# SLIM-MO-64.net
KiCad netlist of a schematic drawn in EAGLE
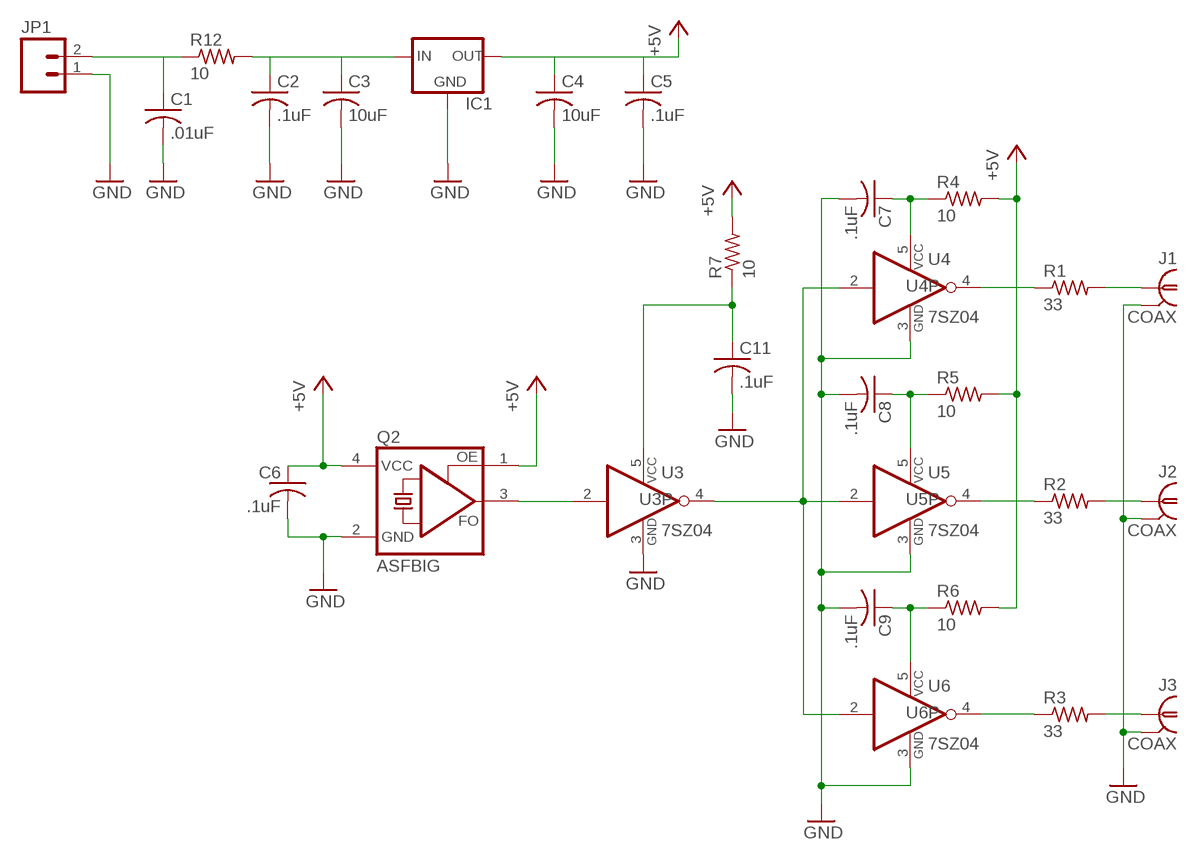
[diagram p0: schematic, sheet 1]

(export (version "E")
  (design (tool "Eeschema 10.0.6"))
  (components
    (comp (ref "C1")
      (value ".01uF")
      (footprint "eagle-import:C0805")
      (libsource (lib "eagle-import") (part "C-USC0805"))
    )
    (comp (ref "C2")
      (value ".1uF")
      (footprint "eagle-import:C0805")
      (libsource (lib "eagle-import") (part "C-USC0805"))
    )
    (comp (ref "C3")
      (value "10uF")
      (footprint "eagle-import:C1206")
      (libsource (lib "eagle-import") (part "C-USC1206"))
    )
    (comp (ref "C4")
      (value "10uF")
      (footprint "eagle-import:C1206")
      (libsource (lib "eagle-import") (part "C-USC1206"))
    )
    (comp (ref "C5")
      (value ".1uF")
      (footprint "eagle-import:C0805")
      (libsource (lib "eagle-import") (part "C-USC0805"))
    )
    (comp (ref "C6")
      (value ".1uF")
      (footprint "eagle-import:C0805")
      (libsource (lib "eagle-import") (part "C-USC0805"))
    )
    (comp (ref "C7")
      (value ".1uF")
      (footprint "eagle-import:C0805")
      (libsource (lib "eagle-import") (part "C-USC0805"))
    )
    (comp (ref "C8")
      (value ".1uF")
      (footprint "eagle-import:C0805")
      (libsource (lib "eagle-import") (part "C-USC0805"))
    )
    (comp (ref "C9")
      (value ".1uF")
      (footprint "eagle-import:C0805")
      (libsource (lib "eagle-import") (part "C-USC0805"))
    )
    (comp (ref "C11")
      (value ".1uF")
      (footprint "eagle-import:C0805")
      (libsource (lib "eagle-import") (part "C-USC0805"))
    )
    (comp (ref "IC1")
      (value "78MXXLDPAK")
      (footprint "eagle-import:TO252")
      (libsource (lib "eagle-import") (part "78MXXLDPAK"))
    )
    (comp (ref "J1")
      (value "COAX")
      (footprint "eagle-import:SLIM_COAX_PAD")
      (libsource (lib "eagle-import") (part "COAX"))
    )
    (comp (ref "J2")
      (value "COAX")
      (footprint "eagle-import:SLIM_COAX_PAD")
      (libsource (lib "eagle-import") (part "COAX"))
    )
    (comp (ref "J3")
      (value "COAX")
      (footprint "eagle-import:SLIM_COAX_PAD")
      (libsource (lib "eagle-import") (part "COAX"))
    )
    (comp (ref "JP1")
      (value "M02POLAR")
      (footprint "eagle-import:MOLEX-1X2")
      (libsource (lib "eagle-import") (part "M02POLAR"))
    )
    (comp (ref "Q2")
      (value "ASFBIG")
      (footprint "eagle-import:CTS507")
      (libsource (lib "eagle-import") (part "ASFBIG"))
    )
    (comp (ref "R1")
      (value "33")
      (footprint "eagle-import:R0805")
      (libsource (lib "eagle-import") (part "R-US_R0805"))
    )
    (comp (ref "R2")
      (value "33")
      (footprint "eagle-import:R0805")
      (libsource (lib "eagle-import") (part "R-US_R0805"))
    )
    (comp (ref "R3")
      (value "33")
      (footprint "eagle-import:R0805")
      (libsource (lib "eagle-import") (part "R-US_R0805"))
    )
    (comp (ref "R4")
      (value "10")
      (footprint "eagle-import:R0805")
      (libsource (lib "eagle-import") (part "R-US_R0805"))
    )
    (comp (ref "R5")
      (value "10")
      (footprint "eagle-import:R0805")
      (libsource (lib "eagle-import") (part "R-US_R0805"))
    )
    (comp (ref "R6")
      (value "10")
      (footprint "eagle-import:R0805")
      (libsource (lib "eagle-import") (part "R-US_R0805"))
    )
    (comp (ref "R7")
      (value "10")
      (footprint "eagle-import:R0805")
      (libsource (lib "eagle-import") (part "R-US_R0805"))
    )
    (comp (ref "R12")
      (value "10")
      (footprint "eagle-import:R0805")
      (libsource (lib "eagle-import") (part "R-US_R0805"))
    )
    (comp (ref "U3")
      (value "7SZ04")
      (footprint "eagle-import:SOT23-5")
      (libsource (lib "eagle-import") (part "741G04DBVAHC"))
    )
    (comp (ref "U4")
      (value "7SZ04")
      (footprint "eagle-import:SOT23-5")
      (libsource (lib "eagle-import") (part "741G04DBVAHC"))
    )
    (comp (ref "U5")
      (value "7SZ04")
      (footprint "eagle-import:SOT23-5")
      (libsource (lib "eagle-import") (part "741G04DBVAHC"))
    )
    (comp (ref "U6")
      (value "7SZ04")
      (footprint "eagle-import:SOT23-5")
      (libsource (lib "eagle-import") (part "741G04DBVAHC"))
    )
  )
  (nets
    (net (code "1") (name "+5V") (class "Default")
      (node (ref "C4") (pin "1") (pinfunction "1_1") (pintype "passive"))
      (node (ref "C5") (pin "1") (pinfunction "1_1") (pintype "passive"))
      (node (ref "C6") (pin "1") (pinfunction "1_1") (pintype "passive"))
      (node (ref "IC1") (pin "2") (pinfunction "OUT_2") (pintype "passive"))
      (node (ref "Q2") (pin "1") (pinfunction "OE_1") (pintype "input"))
      (node (ref "Q2") (pin "4") (pinfunction "VCC_4") (pintype "power_in"))
      (node (ref "R4") (pin "2") (pinfunction "2_2") (pintype "passive"))
      (node (ref "R5") (pin "2") (pinfunction "2_2") (pintype "passive"))
      (node (ref "R6") (pin "2") (pinfunction "2_2") (pintype "passive"))
      (node (ref "R7") (pin "2") (pinfunction "2_2") (pintype "passive"))
    )
    (net (code "2") (name "GND") (class "Default")
      (node (ref "C1") (pin "2") (pinfunction "2_2") (pintype "passive"))
      (node (ref "C11") (pin "2") (pinfunction "2_2") (pintype "passive"))
      (node (ref "C2") (pin "2") (pinfunction "2_2") (pintype "passive"))
      (node (ref "C3") (pin "2") (pinfunction "2_2") (pintype "passive"))
      (node (ref "C4") (pin "2") (pinfunction "2_2") (pintype "passive"))
      (node (ref "C5") (pin "2") (pinfunction "2_2") (pintype "passive"))
      (node (ref "C6") (pin "2") (pinfunction "2_2") (pintype "passive"))
      (node (ref "C7") (pin "2") (pinfunction "2_2") (pintype "passive"))
      (node (ref "C8") (pin "2") (pinfunction "2_2") (pintype "passive"))
      (node (ref "C9") (pin "2") (pinfunction "2_2") (pintype "passive"))
      (node (ref "IC1") (pin "3") (pinfunction "GND_3") (pintype "input"))
      (node (ref "J1") (pin "P$2") (pinfunction "GND_P$2") (pintype "power_in"))
      (node (ref "J2") (pin "P$2") (pinfunction "GND_P$2") (pintype "power_in"))
      (node (ref "J3") (pin "P$2") (pinfunction "GND_P$2") (pintype "power_in"))
      (node (ref "JP1") (pin "1") (pinfunction "1_1") (pintype "passive"))
      (node (ref "Q2") (pin "2") (pinfunction "GND_2") (pintype "power_in"))
      (node (ref "U3") (pin "3") (pinfunction "GND_3") (pintype "power_in"))
      (node (ref "U4") (pin "3") (pinfunction "GND_3") (pintype "power_in"))
      (node (ref "U5") (pin "3") (pinfunction "GND_3") (pintype "power_in"))
      (node (ref "U6") (pin "3") (pinfunction "GND_3") (pintype "power_in"))
    )
    (net (code "3") (name "Net-(C1-Pad1)") (class "Default")
      (node (ref "C1") (pin "1") (pinfunction "1_1") (pintype "passive"))
      (node (ref "JP1") (pin "2") (pinfunction "2_2") (pintype "passive"))
      (node (ref "R12") (pin "1") (pinfunction "1_1") (pintype "passive"))
    )
    (net (code "4") (name "Net-(IC1-IN)") (class "Default")
      (node (ref "C2") (pin "1") (pinfunction "1_1") (pintype "passive"))
      (node (ref "C3") (pin "1") (pinfunction "1_1") (pintype "passive"))
      (node (ref "IC1") (pin "1") (pinfunction "IN_1") (pintype "input"))
      (node (ref "R12") (pin "2") (pinfunction "2_2") (pintype "passive"))
    )
    (net (code "5") (name "Net-(J1-1)") (class "Default")
      (node (ref "J1") (pin "P$1") (pinfunction "1_P$1") (pintype "passive"))
      (node (ref "R1") (pin "2") (pinfunction "2_2") (pintype "passive"))
    )
    (net (code "6") (name "Net-(J2-1)") (class "Default")
      (node (ref "J2") (pin "P$1") (pinfunction "1_P$1") (pintype "passive"))
      (node (ref "R2") (pin "2") (pinfunction "2_2") (pintype "passive"))
    )
    (net (code "7") (name "Net-(J3-1)") (class "Default")
      (node (ref "J3") (pin "P$1") (pinfunction "1_P$1") (pintype "passive"))
      (node (ref "R3") (pin "2") (pinfunction "2_2") (pintype "passive"))
    )
    (net (code "8") (name "Net-(Q2-FO)") (class "Default")
      (node (ref "Q2") (pin "3") (pinfunction "FO_3") (pintype "output"))
      (node (ref "U3") (pin "2") (pinfunction "I_2") (pintype "input"))
    )
    (net (code "9") (name "Net-(U3A-O)") (class "Default")
      (node (ref "U3") (pin "4") (pinfunction "O_4") (pintype "output"))
      (node (ref "U4") (pin "2") (pinfunction "I_2") (pintype "input"))
      (node (ref "U5") (pin "2") (pinfunction "I_2") (pintype "input"))
      (node (ref "U6") (pin "2") (pinfunction "I_2") (pintype "input"))
    )
    (net (code "10") (name "Net-(U3B-VCC)") (class "Default")
      (node (ref "C11") (pin "1") (pinfunction "1_1") (pintype "passive"))
      (node (ref "R7") (pin "1") (pinfunction "1_1") (pintype "passive"))
      (node (ref "U3") (pin "5") (pinfunction "VCC_5") (pintype "power_in"))
    )
    (net (code "11") (name "Net-(U4A-O)") (class "Default")
      (node (ref "R1") (pin "1") (pinfunction "1_1") (pintype "passive"))
      (node (ref "U4") (pin "4") (pinfunction "O_4") (pintype "output"))
    )
    (net (code "12") (name "Net-(U4B-VCC)") (class "Default")
      (node (ref "C7") (pin "1") (pinfunction "1_1") (pintype "passive"))
      (node (ref "R4") (pin "1") (pinfunction "1_1") (pintype "passive"))
      (node (ref "U4") (pin "5") (pinfunction "VCC_5") (pintype "power_in"))
    )
    (net (code "13") (name "Net-(U5A-O)") (class "Default")
      (node (ref "R2") (pin "1") (pinfunction "1_1") (pintype "passive"))
      (node (ref "U5") (pin "4") (pinfunction "O_4") (pintype "output"))
    )
    (net (code "14") (name "Net-(U5B-VCC)") (class "Default")
      (node (ref "C8") (pin "1") (pinfunction "1_1") (pintype "passive"))
      (node (ref "R5") (pin "1") (pinfunction "1_1") (pintype "passive"))
      (node (ref "U5") (pin "5") (pinfunction "VCC_5") (pintype "power_in"))
    )
    (net (code "15") (name "Net-(U6A-O)") (class "Default")
      (node (ref "R3") (pin "1") (pinfunction "1_1") (pintype "passive"))
      (node (ref "U6") (pin "4") (pinfunction "O_4") (pintype "output"))
    )
    (net (code "16") (name "Net-(U6B-VCC)") (class "Default")
      (node (ref "C9") (pin "1") (pinfunction "1_1") (pintype "passive"))
      (node (ref "R6") (pin "1") (pinfunction "1_1") (pintype "passive"))
      (node (ref "U6") (pin "5") (pinfunction "VCC_5") (pintype "power_in"))
    )
  )
)
